# Quad-Stage-Prototype_Supply_V1_0.net
KiCad netlist of a schematic drawn in Altium Designer
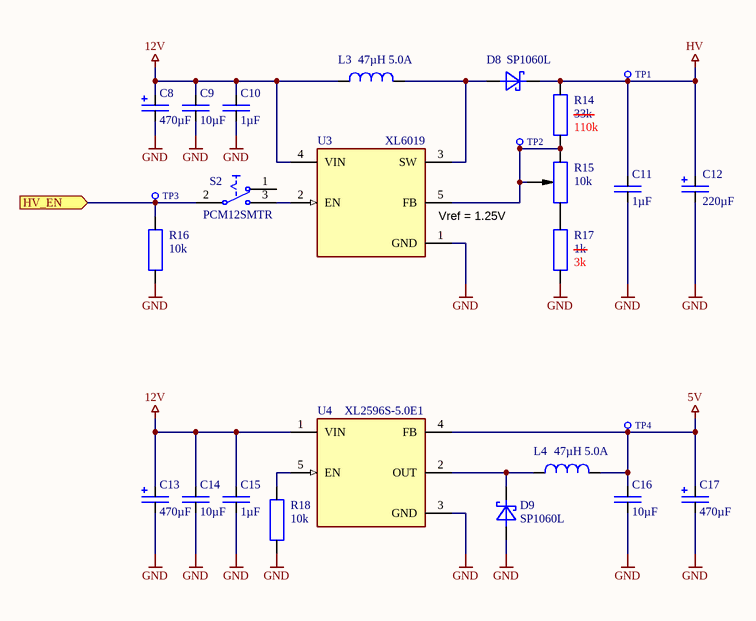
[diagram p0: Quad-Stage-Prototype_Supply_V1.0.SchDoc]

(export (version "E")
  (design (tool "Eeschema 10.0.6"))
  (components
    (comp (ref "C8")
      (value "470µF")
      (footprint "SMD Elko 10.0x10.0")
      (description "CAP-Elko")
      (libsource (lib "TFS Integrated Library") (part "C-ELCAP"))
    )
    (comp (ref "C9")
      (value "10µF")
      (footprint "SMD Keramikkondensator 1206")
      (description "CAP-MK")
      (libsource (lib "AudioAmp") (part "C-CAPACITOR"))
    )
    (comp (ref "C10")
      (value "1µF")
      (footprint "SMD Keramikkondensator 0603")
      (description "CAP-MK")
      (libsource (lib "AudioAmp") (part "C-CAPACITOR"))
    )
    (comp (ref "C11")
      (value "1µF")
      (footprint "SMD Keramikkondensator 1206")
      (description "CAP-MK")
      (libsource (lib "AudioAmp") (part "C-CAPACITOR"))
    )
    (comp (ref "C12")
      (value "220µF")
      (footprint "SMD Elko 12.5x13.5")
      (description "CAP-Elko")
      (libsource (lib "TFS Integrated Library") (part "C-ELCAP"))
    )
    (comp (ref "C13")
      (value "470µF")
      (footprint "SMD Elko 10.0x10.0")
      (description "CAP-Elko")
      (libsource (lib "TFS Integrated Library") (part "C-ELCAP"))
    )
    (comp (ref "C14")
      (value "10µF")
      (footprint "SMD Keramikkondensator 1206")
      (description "CAP-MK")
      (libsource (lib "AudioAmp") (part "C-CAPACITOR"))
    )
    (comp (ref "C15")
      (value "1µF")
      (footprint "SMD Keramikkondensator 0603")
      (description "CAP-MK")
      (libsource (lib "AudioAmp") (part "C-CAPACITOR"))
    )
    (comp (ref "C16")
      (value "10µF")
      (footprint "SMD Keramikkondensator 1206")
      (description "CAP-MK")
      (libsource (lib "AudioAmp") (part "C-CAPACITOR"))
    )
    (comp (ref "C17")
      (value "470µF")
      (footprint "SMD Elko 10.0x10.0")
      (description "CAP-Elko")
      (libsource (lib "TFS Integrated Library") (part "C-ELCAP"))
    )
    (comp (ref "D8")
      (value "SP1060L")
      (footprint "SMD Diode TO-277")
      (description "S-DIODE")
      (libsource (lib "TFS Integrated Library") (part "R-DIODE{colon}SCHKY"))
    )
    (comp (ref "D9")
      (value "SP1060L")
      (footprint "SMD Diode TO-277")
      (description "S-DIODE")
      (libsource (lib "TFS Integrated Library") (part "R-DIODE{colon}SCHKY"))
    )
    (comp (ref "L3")
      (value "47µH 5.0A")
      (footprint "SMD Inductor 13.8x12.6x6.5")
      (description "Shielded Power Inductor")
      (libsource (lib "Nixie-Test") (part "L-COIL"))
    )
    (comp (ref "L4")
      (value "47µH 5.0A")
      (footprint "SMD Inductor 13.8x12.6x6.5")
      (description "Shielded Power Inductor")
      (libsource (lib "") (part "L-COIL_1"))
    )
    (comp (ref "R14")
      (value "33k")
      (footprint "SMD Widerstand 0603")
      (description "RES (E=Heizwiderstand B=Messwandler)")
      (libsource (lib "TFS Integrated Library") (part "R-RESISTOR"))
    )
    (comp (ref "R15")
      (value "10k")
      (footprint "THT Potentiometer (RK09D1130C2P)")
      (description "RES-VAR")
      (libsource (lib "TFS Integrated Library") (part "R-RES{colon}VAR"))
    )
    (comp (ref "R16")
      (value "10k")
      (footprint "SMD Widerstand 0603")
      (description "RES (E=Heizwiderstand B=Messwandler)")
      (libsource (lib "TFS Integrated Library") (part "R-RESISTOR"))
    )
    (comp (ref "R17")
      (value "1k")
      (footprint "SMD Widerstand 0603")
      (description "RES (E=Heizwiderstand B=Messwandler)")
      (libsource (lib "TFS Integrated Library") (part "R-RESISTOR"))
    )
    (comp (ref "R18")
      (value "10k")
      (footprint "SMD Widerstand 0603")
      (description "RES (E=Heizwiderstand B=Messwandler)")
      (libsource (lib "TFS Integrated Library") (part "R-RESISTOR"))
    )
    (comp (ref "S2")
      (value "PCM12SMTR")
      (footprint "SMD Switch SPDT (PCM12SMTR)")
      (description "Miniature Slide Switch")
      (libsource (lib "Custom ST-Link") (part "S-PCM12SMTR"))
    )
    (comp (ref "TP1")
      (value "X-TP")
      (footprint "THT Testpunkt Ø1mm")
      (description "Testpunkt")
      (libsource (lib "Teensy-DevBoard") (part "X-TP"))
    )
    (comp (ref "TP2")
      (value "X-TP")
      (footprint "THT Testpunkt Ø1mm")
      (description "Testpunkt")
      (libsource (lib "Teensy-DevBoard") (part "X-TP"))
    )
    (comp (ref "TP3")
      (value "X-TP")
      (footprint "THT Testpunkt Ø1mm")
      (description "Testpunkt")
      (libsource (lib "Teensy-DevBoard") (part "X-TP"))
    )
    (comp (ref "TP4")
      (value "X-TP")
      (footprint "THT Testpunkt Ø1mm")
      (description "Testpunkt")
      (libsource (lib "Teensy-DevBoard") (part "X-TP"))
    )
    (comp (ref "U3")
      (value "XL6019")
      (footprint "SMD IC TO-263-5")
      (description "High Power Switching Boost Converter")
      (libsource (lib "Quad-Stage-Prototype") (part "U-XL6019"))
    )
    (comp (ref "U4")
      (value "XL2596S-5.0E1")
      (footprint "SMD IC TO-263-5")
      (description "High Power Switching Buck Converter")
      (libsource (lib "Quad-Stage-Prototype") (part "U-XL2596S-5.0E1"))
    )
  )
  (nets
    (net (code "1") (name "/HV_EN") (class "Default")
      (node (ref "R16") (pin "2") (pinfunction "2_2") (pintype "passive"))
      (node (ref "S2") (pin "2") (pinfunction "COMMON1_2") (pintype "passive"))
      (node (ref "TP3") (pin "1") (pinfunction "1_1") (pintype "passive"))
    )
    (net (code "2") (name "5V") (class "Default")
      (node (ref "C16") (pin "2") (pinfunction "2_2") (pintype "passive"))
      (node (ref "C17") (pin "P") (pinfunction "+_P") (pintype "passive"))
      (node (ref "L4") (pin "1") (pinfunction "1_1") (pintype "passive"))
      (node (ref "TP4") (pin "1") (pinfunction "1_1") (pintype "passive"))
      (node (ref "U4") (pin "4") (pinfunction "FB_4") (pintype "passive"))
    )
    (net (code "3") (name "12V") (class "Default")
      (node (ref "C10") (pin "2") (pinfunction "2_2") (pintype "passive"))
      (node (ref "C13") (pin "P") (pinfunction "+_P") (pintype "passive"))
      (node (ref "C14") (pin "2") (pinfunction "2_2") (pintype "passive"))
      (node (ref "C15") (pin "2") (pinfunction "2_2") (pintype "passive"))
      (node (ref "C8") (pin "P") (pinfunction "+_P") (pintype "passive"))
      (node (ref "C9") (pin "2") (pinfunction "2_2") (pintype "passive"))
      (node (ref "L3") (pin "1") (pinfunction "1_1") (pintype "passive"))
      (node (ref "U3") (pin "4") (pinfunction "VIN_4") (pintype "power_in"))
      (node (ref "U4") (pin "1") (pinfunction "VIN_1") (pintype "power_in"))
    )
    (net (code "4") (name "GND") (class "Default")
      (node (ref "C10") (pin "1") (pinfunction "1_1") (pintype "passive"))
      (node (ref "C11") (pin "1") (pinfunction "1_1") (pintype "passive"))
      (node (ref "C12") (pin "M") (pinfunction "-_M") (pintype "passive"))
      (node (ref "C13") (pin "M") (pinfunction "-_M") (pintype "passive"))
      (node (ref "C14") (pin "1") (pinfunction "1_1") (pintype "passive"))
      (node (ref "C15") (pin "1") (pinfunction "1_1") (pintype "passive"))
      (node (ref "C16") (pin "1") (pinfunction "1_1") (pintype "passive"))
      (node (ref "C17") (pin "M") (pinfunction "-_M") (pintype "passive"))
      (node (ref "C8") (pin "M") (pinfunction "-_M") (pintype "passive"))
      (node (ref "C9") (pin "1") (pinfunction "1_1") (pintype "passive"))
      (node (ref "D9") (pin "A") (pinfunction "A_A") (pintype "passive"))
      (node (ref "R16") (pin "1") (pinfunction "1_1") (pintype "passive"))
      (node (ref "R17") (pin "1") (pinfunction "1_1") (pintype "passive"))
      (node (ref "R18") (pin "1") (pinfunction "1_1") (pintype "passive"))
      (node (ref "U3") (pin "1") (pinfunction "GND_1") (pintype "power_in"))
      (node (ref "U4") (pin "3") (pinfunction "GND_3") (pintype "power_in"))
    )
    (net (code "5") (name "HV") (class "Default")
      (node (ref "C11") (pin "2") (pinfunction "2_2") (pintype "passive"))
      (node (ref "C12") (pin "P") (pinfunction "+_P") (pintype "passive"))
      (node (ref "D8") (pin "K") (pinfunction "K_K") (pintype "passive"))
      (node (ref "R14") (pin "2") (pinfunction "2_2") (pintype "passive"))
      (node (ref "TP1") (pin "1") (pinfunction "1_1") (pintype "passive"))
    )
    (net (code "6") (name "Net-(R15-PadCCW)") (class "Default")
      (node (ref "R15") (pin "CCW") (pinfunction "CCW_CCW") (pintype "passive"))
      (node (ref "R17") (pin "2") (pinfunction "2_2") (pintype "passive"))
    )
    (net (code "7") (name "Net-(S2-NO1)") (class "Default")
      (node (ref "S2") (pin "3") (pinfunction "NO1_3") (pintype "passive"))
      (node (ref "U3") (pin "2") (pinfunction "EN_2") (pintype "input"))
    )
    (net (code "8") (name "Net-(U3-FB)") (class "Default")
      (node (ref "R14") (pin "1") (pinfunction "1_1") (pintype "passive"))
      (node (ref "R15") (pin "CW") (pinfunction "CW_CW") (pintype "passive"))
      (node (ref "R15") (pin "M") (pinfunction "M_M") (pintype "passive"))
      (node (ref "TP2") (pin "1") (pinfunction "1_1") (pintype "passive"))
      (node (ref "U3") (pin "5") (pinfunction "FB_5") (pintype "passive"))
    )
    (net (code "9") (name "Net-(U3-SW)") (class "Default")
      (node (ref "D8") (pin "A") (pinfunction "A_A") (pintype "passive"))
      (node (ref "L3") (pin "2") (pinfunction "2_2") (pintype "passive"))
      (node (ref "U3") (pin "3") (pinfunction "SW_3") (pintype "passive"))
    )
    (net (code "10") (name "Net-(U4-EN)") (class "Default")
      (node (ref "R18") (pin "2") (pinfunction "2_2") (pintype "passive"))
      (node (ref "U4") (pin "5") (pinfunction "EN_5") (pintype "input"))
    )
    (net (code "11") (name "Net-(U4-OUT)") (class "Default")
      (node (ref "D9") (pin "K") (pinfunction "K_K") (pintype "passive"))
      (node (ref "L4") (pin "2") (pinfunction "2_2") (pintype "passive"))
      (node (ref "U4") (pin "2") (pinfunction "OUT_2") (pintype "passive"))
    )
    (net (code "12") (name "unconnected-(S2-NC1-Pad1)") (class "Default")
      (node (ref "S2") (pin "1") (pinfunction "NC1_1") (pintype "passive"))
    )
  )
)
